# ATmegaMain.net
KiCad netlist of a schematic drawn in Altium Designer
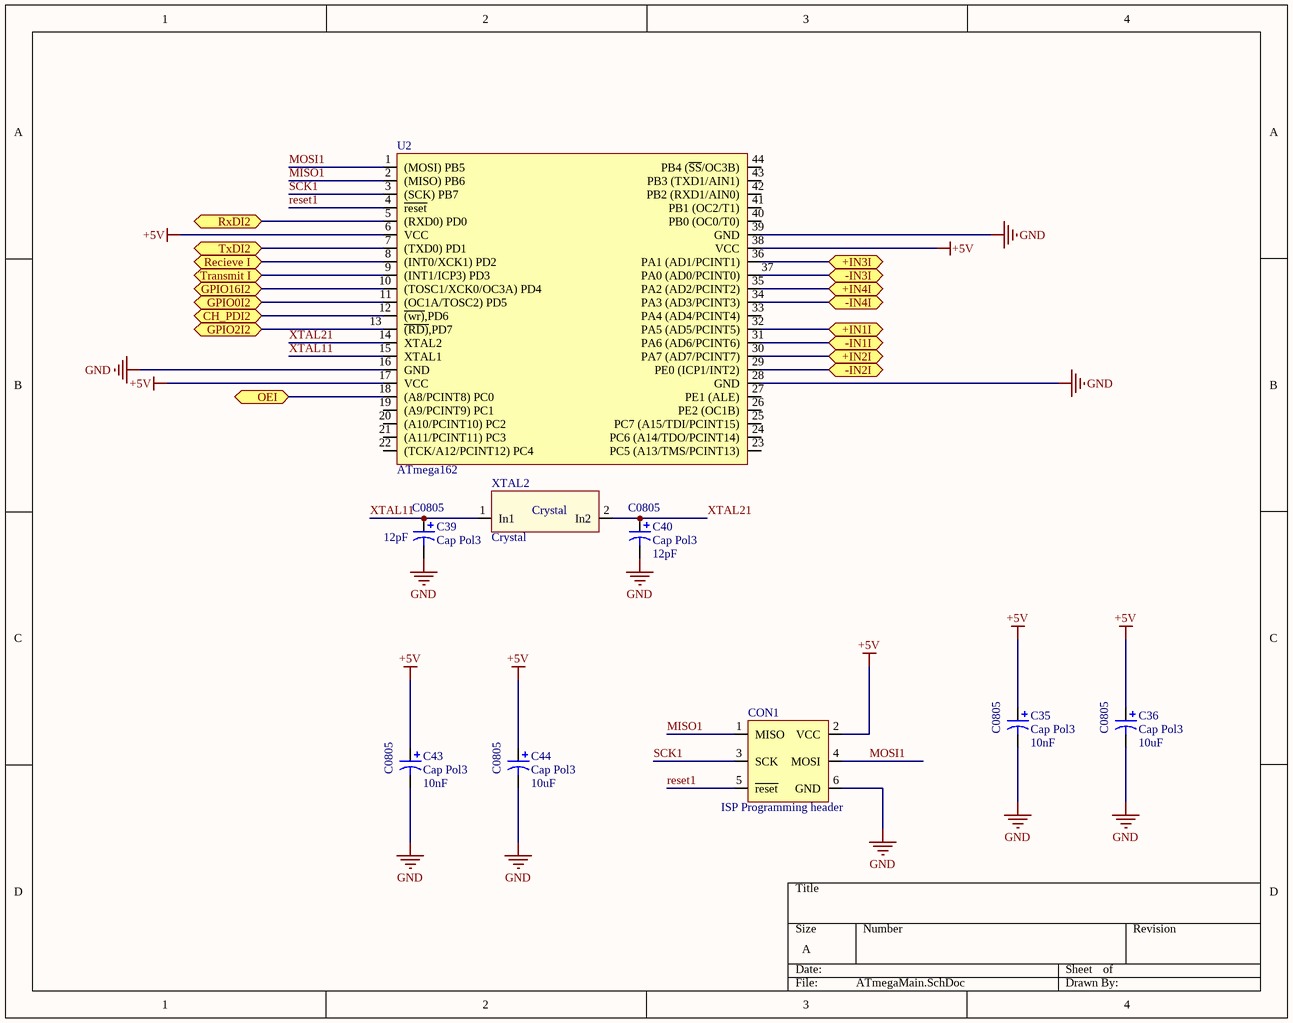
[diagram p0: ATmegaMain.SchDoc]

(export (version "E")
  (design (tool "Eeschema 10.0.6"))
  (components
    (comp (ref "C35")
      (value "Cap Pol3")
      (footprint "C0805")
      (description "Polarized Capacitor (Surface Mount)")
      (fields
        (field (name "PACKAGEREFERENCE") "C0805")
        (field (name "ALTIUM_VALUE") "10nF")
        (field (name "PUBLISHER") "Altium Limited")
      )
      (libsource (lib "Miscellaneous Devices") (part "Cap Pol3"))
    )
    (comp (ref "C36")
      (value "Cap Pol3")
      (footprint "C0805")
      (description "Polarized Capacitor (Surface Mount)")
      (fields
        (field (name "PACKAGEREFERENCE") "C0805")
        (field (name "ALTIUM_VALUE") "10uF")
        (field (name "PUBLISHER") "Altium Limited")
      )
      (libsource (lib "Miscellaneous Devices") (part "Cap Pol3"))
    )
    (comp (ref "C39")
      (value "Cap Pol3")
      (footprint "C0805")
      (description "Polarized Capacitor (Surface Mount)")
      (fields
        (field (name "PACKAGEREFERENCE") "C0805")
        (field (name "ALTIUM_VALUE") "12pF")
        (field (name "PUBLISHER") "Altium Limited")
      )
      (libsource (lib "Miscellaneous Devices") (part "Cap Pol3"))
    )
    (comp (ref "C40")
      (value "Cap Pol3")
      (footprint "C0805")
      (description "Polarized Capacitor (Surface Mount)")
      (fields
        (field (name "PACKAGEREFERENCE") "C0805")
        (field (name "ALTIUM_VALUE") "12pF")
        (field (name "PUBLISHER") "Altium Limited")
      )
      (libsource (lib "Miscellaneous Devices") (part "Cap Pol3"))
    )
    (comp (ref "C43")
      (value "Cap Pol3")
      (footprint "C0805")
      (description "Polarized Capacitor (Surface Mount)")
      (fields
        (field (name "PACKAGEREFERENCE") "C0805")
        (field (name "ALTIUM_VALUE") "10nF")
        (field (name "PUBLISHER") "Altium Limited")
      )
      (libsource (lib "Miscellaneous Devices") (part "Cap Pol3"))
    )
    (comp (ref "C44")
      (value "Cap Pol3")
      (footprint "C0805")
      (description "Polarized Capacitor (Surface Mount)")
      (fields
        (field (name "PACKAGEREFERENCE") "C0805")
        (field (name "ALTIUM_VALUE") "10uF")
        (field (name "PUBLISHER") "Altium Limited")
      )
      (libsource (lib "Miscellaneous Devices") (part "Cap Pol3"))
    )
    (comp (ref "CON1")
      (value "ISP Programming header")
      (footprint "ISP programming header")
      (libsource (lib "ATMEGA126") (part "ISP Programming header"))
    )
    (comp (ref "U2")
      (value "ATmega162")
      (footprint "ATmga162")
      (libsource (lib "ATMEGA126") (part "ATmega162"))
    )
    (comp (ref "XTAL2")
      (value "Crystal")
      (footprint "Crystal")
      (libsource (lib "ATMEGA126") (part "Crystal"))
    )
  )
  (nets
    (net (code "1") (name "+5V") (class "Default")
      (node (ref "C35") (pin "1") (pinfunction "1_1") (pintype "passive"))
      (node (ref "C36") (pin "1") (pinfunction "1_1") (pintype "passive"))
      (node (ref "C43") (pin "1") (pinfunction "1_1") (pintype "passive"))
      (node (ref "C44") (pin "1") (pinfunction "1_1") (pintype "passive"))
      (node (ref "CON1") (pin "2") (pinfunction "VCC_2") (pintype "power_in"))
      (node (ref "U2") (pin "17") (pinfunction "VCC_17") (pintype "passive"))
      (node (ref "U2") (pin "38") (pinfunction "VCC_38") (pintype "passive"))
      (node (ref "U2") (pin "6") (pinfunction "VCC_6") (pintype "passive"))
    )
    (net (code "2") (name "/+IN1I") (class "Default")
      (node (ref "U2") (pin "32") (pinfunction "PA5_(AD5/PCINT5)_32") (pintype "passive"))
    )
    (net (code "3") (name "/+IN2I") (class "Default")
      (node (ref "U2") (pin "30") (pinfunction "PA7_(AD7/PCINT7)_30") (pintype "passive"))
    )
    (net (code "4") (name "/+IN3I") (class "Default")
      (node (ref "U2") (pin "36") (pinfunction "PA1_(AD1/PCINT1)_36") (pintype "passive"))
    )
    (net (code "5") (name "/+IN4I") (class "Default")
      (node (ref "U2") (pin "35") (pinfunction "PA2_(AD2/PCINT2)_35") (pintype "passive"))
    )
    (net (code "6") (name "/-IN1I") (class "Default")
      (node (ref "U2") (pin "31") (pinfunction "PA6_(AD6/PCINT6)_31") (pintype "passive"))
    )
    (net (code "7") (name "/-IN2I") (class "Default")
      (node (ref "U2") (pin "29") (pinfunction "PE0_(ICP1/INT2)_29") (pintype "passive"))
    )
    (net (code "8") (name "/-IN3I") (class "Default")
      (node (ref "U2") (pin "37") (pinfunction "PA0_(AD0/PCINT0)_37") (pintype "passive"))
    )
    (net (code "9") (name "/-IN4I") (class "Default")
      (node (ref "U2") (pin "34") (pinfunction "PA3_(AD3/PCINT3)_34") (pintype "passive"))
    )
    (net (code "10") (name "/CH_PDI2") (class "Default")
      (node (ref "U2") (pin "12") (pinfunction "~{(wr)},PD6_12") (pintype "passive"))
    )
    (net (code "11") (name "/GPIO0I2") (class "Default")
      (node (ref "U2") (pin "11") (pinfunction "(OC1A/TOSC2)_PD5_11") (pintype "passive"))
    )
    (net (code "12") (name "/GPIO2I2") (class "Default")
      (node (ref "U2") (pin "13") (pinfunction "~{(RD)},PD7_13") (pintype "passive"))
    )
    (net (code "13") (name "/GPIO16I2") (class "Default")
      (node (ref "U2") (pin "10") (pinfunction "(TOSC1/XCK0/OC3A)_PD4_10") (pintype "passive"))
    )
    (net (code "14") (name "/MISO1") (class "Default")
      (node (ref "CON1") (pin "1") (pinfunction "MISO_1") (pintype "passive"))
      (node (ref "U2") (pin "2") (pinfunction "(MISO)_PB6_2") (pintype "passive"))
    )
    (net (code "15") (name "/MOSI1") (class "Default")
      (node (ref "CON1") (pin "4") (pinfunction "MOSI_4") (pintype "passive"))
      (node (ref "U2") (pin "1") (pinfunction "(MOSI)_PB5_1") (pintype "passive"))
    )
    (net (code "16") (name "/OEI") (class "Default")
      (node (ref "U2") (pin "18") (pinfunction "(A8/PCINT8)_PC0_18") (pintype "passive"))
    )
    (net (code "17") (name "/Recieve I") (class "Default")
      (node (ref "U2") (pin "8") (pinfunction "(INT0/XCK1)_PD2_8") (pintype "passive"))
    )
    (net (code "18") (name "/RxDI2") (class "Default")
      (node (ref "U2") (pin "5") (pinfunction "(RXD0)_PD0_5") (pintype "passive"))
    )
    (net (code "19") (name "/SCK1") (class "Default")
      (node (ref "CON1") (pin "3") (pinfunction "SCK_3") (pintype "passive"))
      (node (ref "U2") (pin "3") (pinfunction "(SCK)_PB7_3") (pintype "passive"))
    )
    (net (code "20") (name "/Transmit I") (class "Default")
      (node (ref "U2") (pin "9") (pinfunction "(INT1/ICP3)_PD3_9") (pintype "passive"))
    )
    (net (code "21") (name "/TxDI2") (class "Default")
      (node (ref "U2") (pin "7") (pinfunction "(TXD0)_PD1_7") (pintype "passive"))
    )
    (net (code "22") (name "/XTAL11") (class "Default")
      (node (ref "C39") (pin "1") (pinfunction "1_1") (pintype "passive"))
      (node (ref "U2") (pin "15") (pinfunction "XTAL1_15") (pintype "passive"))
      (node (ref "XTAL2") (pin "1") (pinfunction "In1_1") (pintype "passive"))
    )
    (net (code "23") (name "/XTAL21") (class "Default")
      (node (ref "C40") (pin "1") (pinfunction "1_1") (pintype "passive"))
      (node (ref "U2") (pin "14") (pinfunction "XTAL2_14") (pintype "passive"))
      (node (ref "XTAL2") (pin "2") (pinfunction "In2_2") (pintype "passive"))
    )
    (net (code "24") (name "/reset1") (class "Default")
      (node (ref "CON1") (pin "5") (pinfunction "~{reset}_5") (pintype "passive"))
      (node (ref "U2") (pin "4") (pinfunction "~{reset}_4") (pintype "passive"))
    )
    (net (code "25") (name "GND") (class "Default")
      (node (ref "C35") (pin "2") (pinfunction "2_2") (pintype "passive"))
      (node (ref "C36") (pin "2") (pinfunction "2_2") (pintype "passive"))
      (node (ref "C39") (pin "2") (pinfunction "2_2") (pintype "passive"))
      (node (ref "C40") (pin "2") (pinfunction "2_2") (pintype "passive"))
      (node (ref "C43") (pin "2") (pinfunction "2_2") (pintype "passive"))
      (node (ref "C44") (pin "2") (pinfunction "2_2") (pintype "passive"))
      (node (ref "CON1") (pin "6") (pinfunction "GND_6") (pintype "power_in"))
      (node (ref "U2") (pin "16") (pinfunction "GND_16") (pintype "passive"))
      (node (ref "U2") (pin "28") (pinfunction "GND_28") (pintype "passive"))
      (node (ref "U2") (pin "39") (pinfunction "GND_39") (pintype "passive"))
    )
    (net (code "26") (name "unconnected-(U2-(A9{slash}PCINT9)_PC1-Pad19)") (class "Default")
      (node (ref "U2") (pin "19") (pinfunction "(A9/PCINT9)_PC1_19") (pintype "passive"))
    )
    (net (code "27") (name "unconnected-(U2-(A10{slash}PCINT10)_PC2-Pad20)") (class "Default")
      (node (ref "U2") (pin "20") (pinfunction "(A10/PCINT10)_PC2_20") (pintype "passive"))
    )
    (net (code "28") (name "unconnected-(U2-(A11{slash}PCINT11)_PC3-Pad21)") (class "Default")
      (node (ref "U2") (pin "21") (pinfunction "(A11/PCINT11)_PC3_21") (pintype "passive"))
    )
    (net (code "29") (name "unconnected-(U2-(TCK{slash}A12{slash}PCINT12)_PC4-Pad22)") (class "Default")
      (node (ref "U2") (pin "22") (pinfunction "(TCK/A12/PCINT12)_PC4_22") (pintype "passive"))
    )
    (net (code "30") (name "unconnected-(U2-PA4_(AD4{slash}PCINT4)-Pad33)") (class "Default")
      (node (ref "U2") (pin "33") (pinfunction "PA4_(AD4/PCINT4)_33") (pintype "passive"))
    )
    (net (code "31") (name "unconnected-(U2-PB0_(OC0{slash}T0)-Pad40)") (class "Default")
      (node (ref "U2") (pin "40") (pinfunction "PB0_(OC0/T0)_40") (pintype "passive"))
    )
    (net (code "32") (name "unconnected-(U2-PB1_(OC2{slash}T1)-Pad41)") (class "Default")
      (node (ref "U2") (pin "41") (pinfunction "PB1_(OC2/T1)_41") (pintype "passive"))
    )
    (net (code "33") (name "unconnected-(U2-PB2_(RXD1{slash}AIN0)-Pad42)") (class "Default")
      (node (ref "U2") (pin "42") (pinfunction "PB2_(RXD1/AIN0)_42") (pintype "passive"))
    )
    (net (code "34") (name "unconnected-(U2-PB3_(TXD1{slash}AIN1)-Pad43)") (class "Default")
      (node (ref "U2") (pin "43") (pinfunction "PB3_(TXD1/AIN1)_43") (pintype "passive"))
    )
    (net (code "35") (name "unconnected-(U2-PB4_(~{SS}{slash}OC3B)-Pad44)") (class "Default")
      (node (ref "U2") (pin "44") (pinfunction "PB4_(~{SS}/OC3B)_44") (pintype "passive"))
    )
    (net (code "36") (name "unconnected-(U2-PC5_(A13{slash}TMS{slash}PCINT13)-Pad23)") (class "Default")
      (node (ref "U2") (pin "23") (pinfunction "PC5_(A13/TMS/PCINT13)_23") (pintype "passive"))
    )
    (net (code "37") (name "unconnected-(U2-PC6_(A14{slash}TDO{slash}PCINT14)-Pad24)") (class "Default")
      (node (ref "U2") (pin "24") (pinfunction "PC6_(A14/TDO/PCINT14)_24") (pintype "passive"))
    )
    (net (code "38") (name "unconnected-(U2-PC7_(A15{slash}TDI{slash}PCINT15)-Pad25)") (class "Default")
      (node (ref "U2") (pin "25") (pinfunction "PC7_(A15/TDI/PCINT15)_25") (pintype "passive"))
    )
    (net (code "39") (name "unconnected-(U2-PE1_(ALE)-Pad27)") (class "Default")
      (node (ref "U2") (pin "27") (pinfunction "PE1_(ALE)_27") (pintype "passive"))
    )
    (net (code "40") (name "unconnected-(U2-PE2_(OC1B)-Pad26)") (class "Default")
      (node (ref "U2") (pin "26") (pinfunction "PE2_(OC1B)_26") (pintype "passive"))
    )
  )
)
